# PWR_MNG_V1_0.net
KiCad netlist of a schematic drawn in Altium Designer
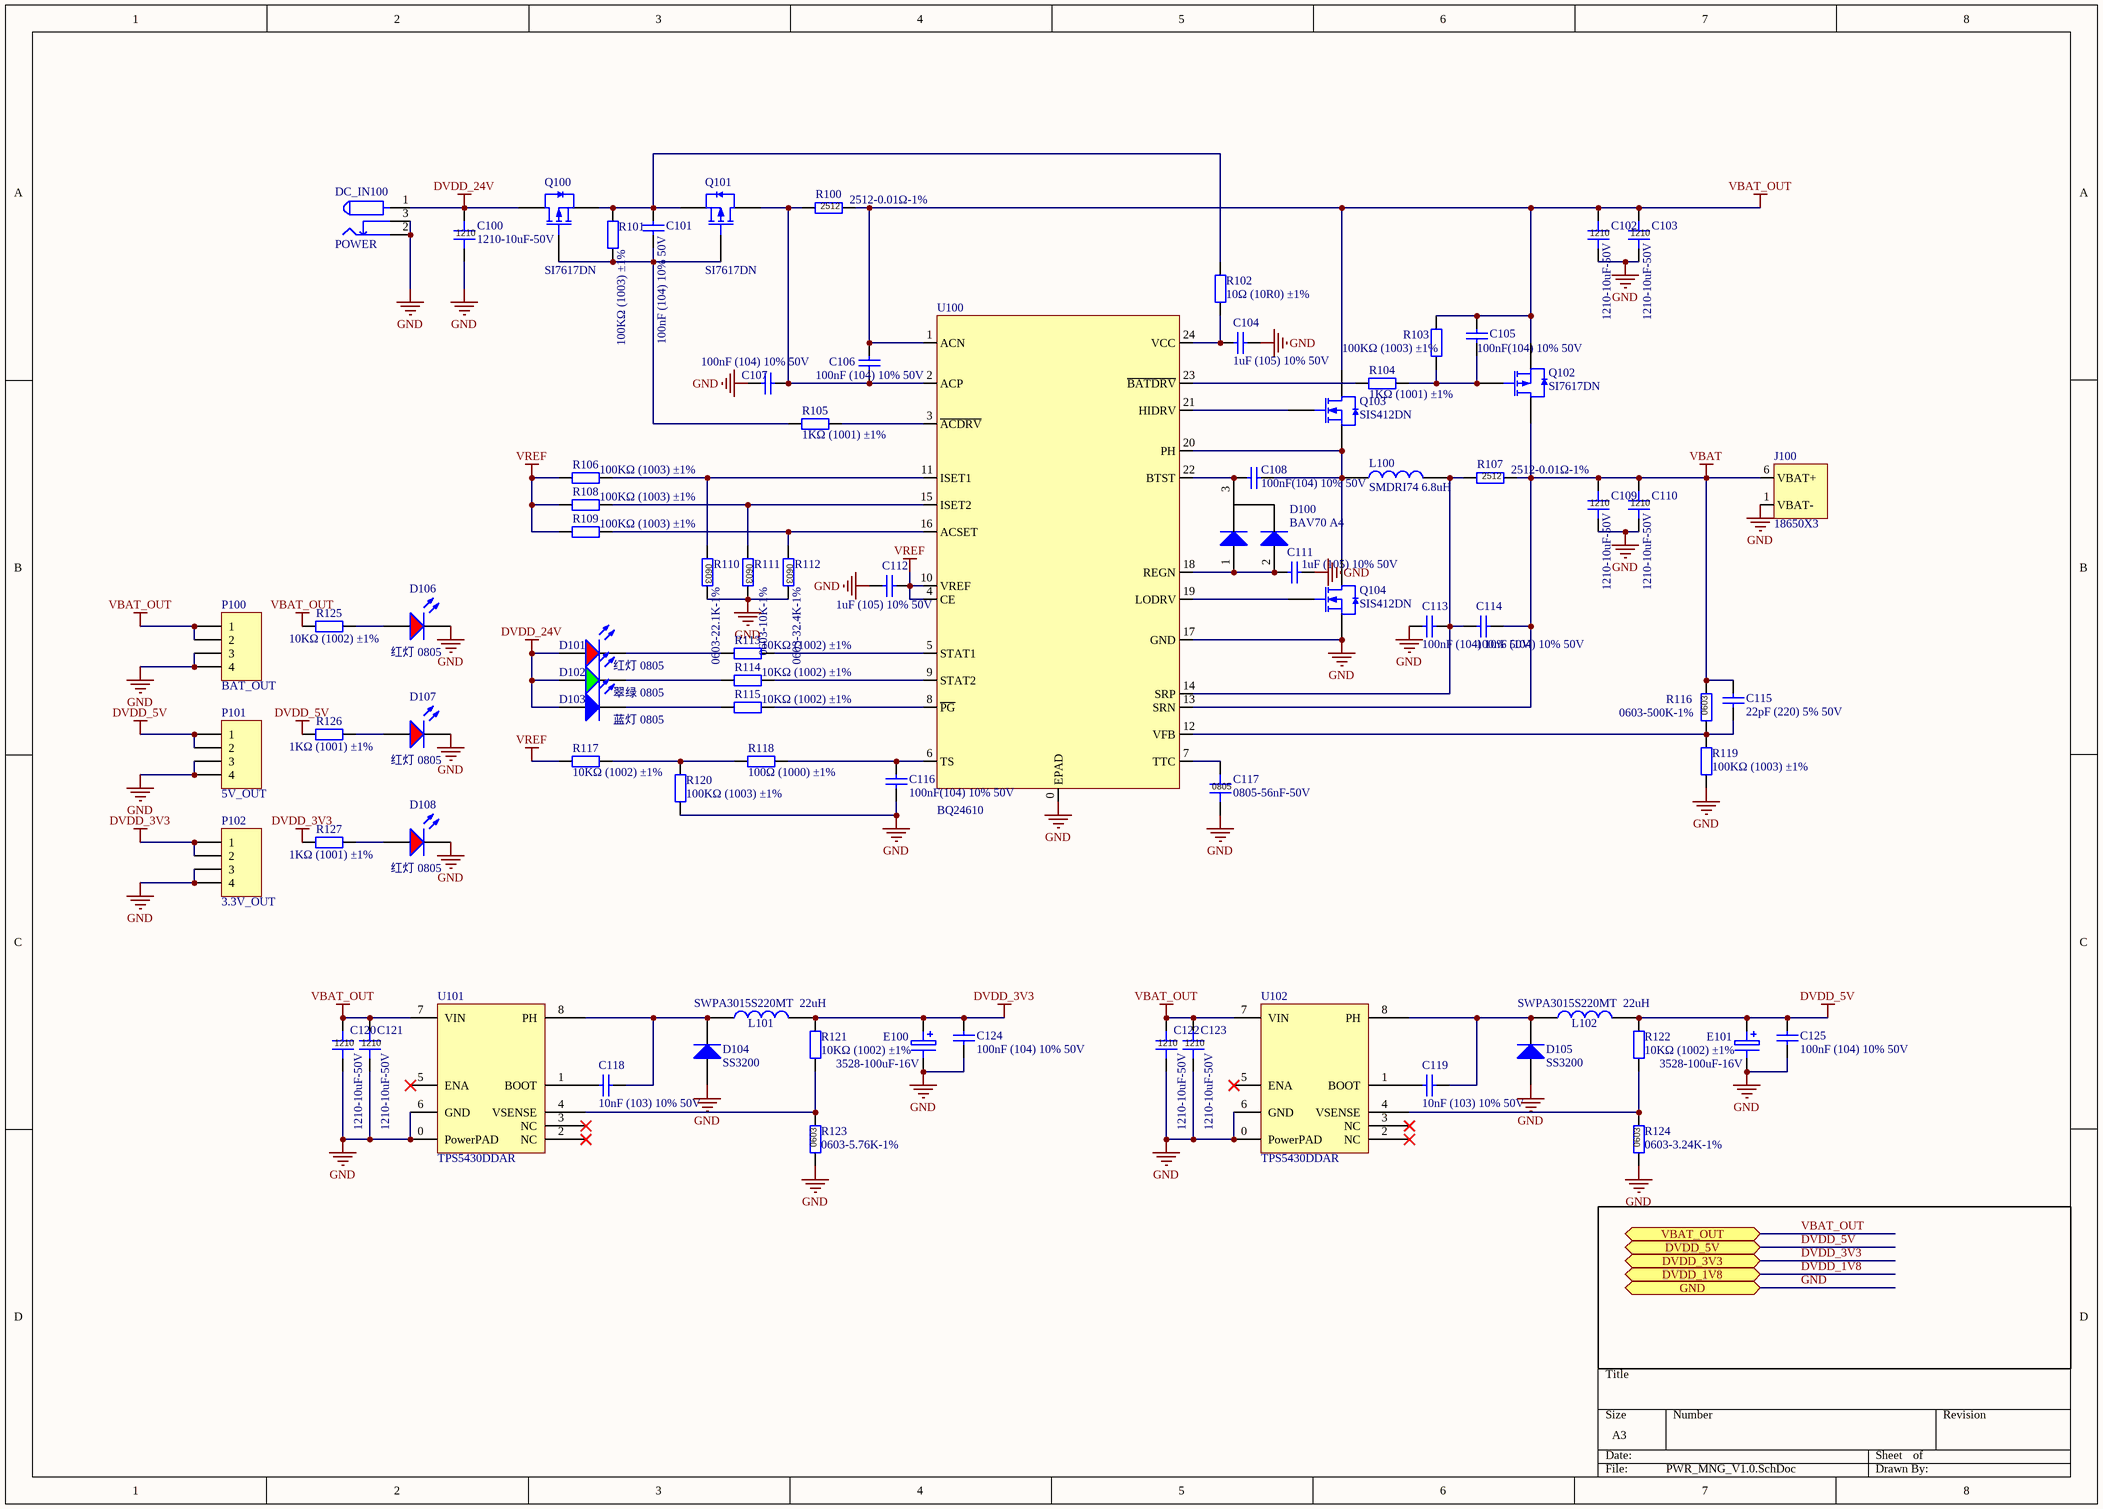
[diagram p0: PWR_MNG_V1.0.SchDoc]

(export (version "E")
  (design (tool "Eeschema 10.0.6"))
  (components
    (comp (ref "C100")
      (value "1210-10uF-50V")
      (footprint "1210_C")
      (description "贴片电容")
      (libsource (lib "JC_Integrated_Library") (part "1210 10uF (106) 10% 50V"))
    )
    (comp (ref "C101")
      (value "100nF (104) 10% 50V")
      (footprint "0603_C")
      (description "贴片电容")
      (libsource (lib "Miscellaneous Devices LC") (part "0603 100nF (104) 10% 50V"))
    )
    (comp (ref "C102")
      (value "1210-10uF-50V")
      (footprint "1210_C")
      (description "贴片电容")
      (libsource (lib "JC_Integrated_Library") (part "1210 10uF (106) 10% 50V"))
    )
    (comp (ref "C103")
      (value "1210-10uF-50V")
      (footprint "1210_C")
      (description "贴片电容")
      (libsource (lib "JC_Integrated_Library") (part "1210 10uF (106) 10% 50V"))
    )
    (comp (ref "C104")
      (value "1uF (105) 10% 50V")
      (footprint "0805_C")
      (description "贴片电容")
      (libsource (lib "Miscellaneous Devices LC") (part "0805 1uF (105) 10% 50V"))
    )
    (comp (ref "C105")
      (value "100nF(104) 10% 50V")
      (footprint "0805_C")
      (description "贴片电容")
      (libsource (lib "Miscellaneous Devices LC") (part "0805 100nF(104) 10% 50V"))
    )
    (comp (ref "C106")
      (value "100nF (104) 10% 50V")
      (footprint "0603_C")
      (description "贴片电容")
      (libsource (lib "Miscellaneous Devices LC") (part "0603 100nF (104) 10% 50V"))
    )
    (comp (ref "C107")
      (value "100nF (104) 10% 50V")
      (footprint "0603_C")
      (description "贴片电容")
      (libsource (lib "Miscellaneous Devices LC") (part "0603 100nF (104) 10% 50V"))
    )
    (comp (ref "C108")
      (value "100nF(104) 10% 50V")
      (footprint "0805_C")
      (description "贴片电容")
      (libsource (lib "Miscellaneous Devices LC") (part "0805 100nF(104) 10% 50V"))
    )
    (comp (ref "C109")
      (value "1210-10uF-50V")
      (footprint "1210_C")
      (description "贴片电容")
      (libsource (lib "JC_Integrated_Library") (part "1210 10uF (106) 10% 50V"))
    )
    (comp (ref "C110")
      (value "1210-10uF-50V")
      (footprint "1210_C")
      (description "贴片电容")
      (libsource (lib "JC_Integrated_Library") (part "1210 10uF (106) 10% 50V"))
    )
    (comp (ref "C111")
      (value "1uF (105) 10% 50V")
      (footprint "0805_C")
      (description "贴片电容")
      (libsource (lib "Miscellaneous Devices LC") (part "0805 1uF (105) 10% 50V"))
    )
    (comp (ref "C112")
      (value "1uF (105) 10% 50V")
      (footprint "0805_C")
      (description "贴片电容")
      (libsource (lib "Miscellaneous Devices LC") (part "0805 1uF (105) 10% 50V"))
    )
    (comp (ref "C113")
      (value "100nF (104) 10% 50V")
      (footprint "0603_C")
      (description "贴片电容")
      (libsource (lib "Miscellaneous Devices LC") (part "0603 100nF (104) 10% 50V"))
    )
    (comp (ref "C114")
      (value "100nF (104) 10% 50V")
      (footprint "0603_C")
      (description "贴片电容")
      (libsource (lib "Miscellaneous Devices LC") (part "0603 100nF (104) 10% 50V"))
    )
    (comp (ref "C115")
      (value "22pF (220) 5% 50V")
      (footprint "0603_C")
      (description "贴片电容")
      (libsource (lib "Miscellaneous Devices LC") (part "0603 22pF (220) 5% 50V"))
    )
    (comp (ref "C116")
      (value "100nF(104) 10% 50V")
      (footprint "0805_C")
      (description "贴片电容")
      (libsource (lib "Miscellaneous Devices LC") (part "0805 100nF(104) 10% 50V"))
    )
    (comp (ref "C117")
      (value "0805-56nF-50V")
      (footprint "0805_C")
      (description "贴片电容")
      (libsource (lib "JC_Integrated_Library") (part "0805 100nF (104) 10% 50V"))
    )
    (comp (ref "C118")
      (value "10nF (103) 10% 50V")
      (footprint "0603_C")
      (description "贴片电容")
      (libsource (lib "Miscellaneous Devices LC") (part "0603 10nF (103) 10% 50V"))
    )
    (comp (ref "C119")
      (value "10nF (103) 10% 50V")
      (footprint "0603_C")
      (description "贴片电容")
      (libsource (lib "Miscellaneous Devices LC") (part "0603 10nF (103) 10% 50V"))
    )
    (comp (ref "C120")
      (value "1210-10uF-50V")
      (footprint "1210_C")
      (description "贴片电容")
      (libsource (lib "JC_Integrated_Library") (part "1210 10uF (106) 10% 50V"))
    )
    (comp (ref "C121")
      (value "1210-10uF-50V")
      (footprint "1210_C")
      (description "贴片电容")
      (libsource (lib "JC_Integrated_Library") (part "1210 10uF (106) 10% 50V"))
    )
    (comp (ref "C122")
      (value "1210-10uF-50V")
      (footprint "1210_C")
      (description "贴片电容")
      (libsource (lib "JC_Integrated_Library") (part "1210 10uF (106) 10% 50V"))
    )
    (comp (ref "C123")
      (value "1210-10uF-50V")
      (footprint "1210_C")
      (description "贴片电容")
      (libsource (lib "JC_Integrated_Library") (part "1210 10uF (106) 10% 50V"))
    )
    (comp (ref "C124")
      (value "100nF (104) 10% 50V")
      (footprint "0603_C")
      (description "贴片电容")
      (libsource (lib "Miscellaneous Devices LC") (part "0603 100nF (104) 10% 50V"))
    )
    (comp (ref "C125")
      (value "100nF (104) 10% 50V")
      (footprint "0603_C")
      (description "贴片电容")
      (libsource (lib "Miscellaneous Devices LC") (part "0603 100nF (104) 10% 50V"))
    )
    (comp (ref "D100")
      (value "BAV70 A4")
      (footprint "SOT-23(SOT-23-3)")
      (description "开关二极管")
      (libsource (lib "Miscellaneous Devices LC") (part "SOT-23 BAV70 A4"))
    )
    (comp (ref "D101")
      (value "红灯 0805")
      (footprint "0805_LED_S1")
      (description "发光二极管")
      (libsource (lib "Miscellaneous Devices LC") (part "0805 红灯"))
    )
    (comp (ref "D102")
      (value "翠绿 0805")
      (footprint "0805_LED_S1")
      (description "发光二极管")
      (libsource (lib "Miscellaneous Devices LC") (part "0805 翠绿"))
    )
    (comp (ref "D103")
      (value "蓝灯 0805")
      (footprint "0805_LED_S1")
      (description "发光二极管")
      (libsource (lib "Miscellaneous Devices LC") (part "0805 蓝灯"))
    )
    (comp (ref "D104")
      (value "SS3200")
      (footprint "SMA(DO-214AC)_S1")
      (description "二极管")
      (libsource (lib "Miscellaneous Devices LC") (part "SMA(DO-214AC) M7"))
    )
    (comp (ref "D105")
      (value "SS3200")
      (footprint "SMA(DO-214AC)_S1")
      (description "二极管")
      (libsource (lib "Miscellaneous Devices LC") (part "SMA(DO-214AC) M7"))
    )
    (comp (ref "D106")
      (value "红灯 0805")
      (footprint "0805_LED_S1")
      (description "发光二极管")
      (libsource (lib "Miscellaneous Devices LC") (part "0805 红灯"))
    )
    (comp (ref "D107")
      (value "红灯 0805")
      (footprint "0805_LED_S1")
      (description "发光二极管")
      (libsource (lib "Miscellaneous Devices LC") (part "0805 红灯"))
    )
    (comp (ref "D108")
      (value "红灯 0805")
      (footprint "0805_LED_S1")
      (description "发光二极管")
      (libsource (lib "Miscellaneous Devices LC") (part "0805 红灯"))
    )
    (comp (ref "DC_IN100")
      (value "POWER")
      (footprint "DC002")
      (libsource (lib "JC_Integrated_Library") (part "PWR"))
    )
    (comp (ref "E100")
      (value "3528-100uF-16V")
      (footprint "ES_3528")
      (description "贴片钽电容")
      (libsource (lib "JC_Integrated_Library") (part "ES-3528"))
    )
    (comp (ref "E101")
      (value "3528-100uF-16V")
      (footprint "ES_3528")
      (description "贴片钽电容")
      (libsource (lib "JC_Integrated_Library") (part "ES-3528"))
    )
    (comp (ref "J100")
      (value "18650X3")
      (footprint "18650X3")
      (description "BAT_BASE")
      (libsource (lib "JC_Integrated_Library") (part "18650X3"))
    )
    (comp (ref "L100")
      (value "SMDRI74 6.8uH")
      (footprint "L 7.5*7.5*4.5")
      (description "贴片电感")
      (libsource (lib "JC_Integrated_Library") (part "10uH 20%"))
    )
    (comp (ref "L101")
      (value "SWPA3015S220MT  22uH")
      (footprint "L 3.0*3.0*1.5")
      (description "贴片电感")
      (libsource (lib "JC_Integrated_Library") (part "10uH 20%"))
    )
    (comp (ref "L102")
      (value "SWPA3015S220MT  22uH")
      (footprint "L 3.0*3.0*1.5")
      (description "贴片电感")
      (libsource (lib "JC_Integrated_Library") (part "10uH 20%"))
    )
    (comp (ref "P100")
      (value "BAT_OUT")
      (footprint "HDR1X4")
      (description "Header, 4-Pin")
      (fields (field (name "PUBLISHER") "Altium Limited"))
      (libsource (lib "Miscellaneous Connectors") (part "Header 4"))
    )
    (comp (ref "P101")
      (value "5V_OUT")
      (footprint "HDR1X4")
      (description "Header, 4-Pin")
      (fields (field (name "PUBLISHER") "Altium Limited"))
      (libsource (lib "Miscellaneous Connectors") (part "Header 4"))
    )
    (comp (ref "P102")
      (value "3.3V_OUT")
      (footprint "HDR1X4")
      (description "Header, 4-Pin")
      (fields (field (name "PUBLISHER") "Altium Limited"))
      (libsource (lib "Miscellaneous Connectors") (part "Header 4"))
    )
    (comp (ref "Q100")
      (value "SI7617DN")
      (footprint "PAK-1212-8")
      (description "P-MOS")
      (libsource (lib "JC_Integrated_Library") (part "SI7617DN"))
    )
    (comp (ref "Q101")
      (value "SI7617DN")
      (footprint "PAK-1212-8")
      (description "P-MOS")
      (libsource (lib "JC_Integrated_Library") (part "SI7617DN"))
    )
    (comp (ref "Q102")
      (value "SI7617DN")
      (footprint "PAK-1212-8")
      (description "P-MOS")
      (libsource (lib "JC_Integrated_Library") (part "SI7617DN"))
    )
    (comp (ref "Q103")
      (value "SIS412DN")
      (footprint "PAK-1212-8")
      (description "N-MOS")
      (libsource (lib "JC_Integrated_Library") (part "SIS412DN"))
    )
    (comp (ref "Q104")
      (value "SIS412DN")
      (footprint "PAK-1212-8")
      (description "N-MOS")
      (libsource (lib "JC_Integrated_Library") (part "SIS412DN"))
    )
    (comp (ref "R100")
      (value "2512-0.01Ω-1%")
      (footprint "2512_R")
      (description "贴片电阻")
      (libsource (lib "JC_Integrated_Library") (part "2512 10KΩ (103) 1%"))
    )
    (comp (ref "R101")
      (value "100KΩ (1003) ±1%")
      (footprint "0603_R")
      (description "贴片电阻")
      (libsource (lib "Miscellaneous Devices LC") (part "0603 100KΩ (1003) 1%"))
    )
    (comp (ref "R102")
      (value "10Ω (10R0) ±1%")
      (footprint "0805_R")
      (description "贴片电阻")
      (libsource (lib "Miscellaneous Devices LC") (part "0805 10Ω (10R0) 1%"))
    )
    (comp (ref "R103")
      (value "100KΩ (1003) ±1%")
      (footprint "0805_R")
      (description "贴片电阻")
      (libsource (lib "Miscellaneous Devices LC") (part "0805 100KΩ (1003) 1%"))
    )
    (comp (ref "R104")
      (value "1KΩ (1001) ±1%")
      (footprint "0805_R")
      (description "贴片电阻")
      (libsource (lib "Miscellaneous Devices LC") (part "0805 1KΩ (1001) 1%"))
    )
    (comp (ref "R105")
      (value "1KΩ (1001) ±1%")
      (footprint "0603_R")
      (description "贴片电阻")
      (libsource (lib "Miscellaneous Devices LC") (part "0603 1KΩ (1001) 1%"))
    )
    (comp (ref "R106")
      (value "100KΩ (1003) ±1%")
      (footprint "0603_R")
      (description "贴片电阻")
      (libsource (lib "") (part "0603 100KΩ (1003) 1%_1"))
    )
    (comp (ref "R107")
      (value "2512-0.01Ω-1%")
      (footprint "2512_R")
      (description "贴片电阻")
      (libsource (lib "JC_Integrated_Library") (part "2512 10KΩ (103) 1%"))
    )
    (comp (ref "R108")
      (value "100KΩ (1003) ±1%")
      (footprint "0603_R")
      (description "贴片电阻")
      (libsource (lib "") (part "0603 100KΩ (1003) 1%_1"))
    )
    (comp (ref "R109")
      (value "100KΩ (1003) ±1%")
      (footprint "0603_R")
      (description "贴片电阻")
      (libsource (lib "") (part "0603 100KΩ (1003) 1%_1"))
    )
    (comp (ref "R110")
      (value "0603-22.1K-1%")
      (footprint "0603_R")
      (description "贴片电阻")
      (libsource (lib "") (part "0603 10KΩ (103) 1%_1"))
    )
    (comp (ref "R111")
      (value "0603-10K-1%")
      (footprint "0603_R")
      (description "贴片电阻")
      (libsource (lib "") (part "0603 10KΩ (103) 1%_1"))
    )
    (comp (ref "R112")
      (value "0603-32.4K-1%")
      (footprint "0603_R")
      (description "贴片电阻")
      (libsource (lib "") (part "0603 10KΩ (103) 1%_1"))
    )
    (comp (ref "R113")
      (value "10KΩ (1002) ±1%")
      (footprint "0805_R")
      (description "贴片电阻")
      (libsource (lib "Miscellaneous Devices LC") (part "0805 10KΩ (1002) 1%"))
    )
    (comp (ref "R114")
      (value "10KΩ (1002) ±1%")
      (footprint "0805_R")
      (description "贴片电阻")
      (libsource (lib "Miscellaneous Devices LC") (part "0805 10KΩ (1002) 1%"))
    )
    (comp (ref "R115")
      (value "10KΩ (1002) ±1%")
      (footprint "0805_R")
      (description "贴片电阻")
      (libsource (lib "Miscellaneous Devices LC") (part "0805 10KΩ (1002) 1%"))
    )
    (comp (ref "R116")
      (value "0603-500K-1%")
      (footprint "0603_R")
      (description "贴片电阻")
      (libsource (lib "JC_Integrated_Library") (part "0603 10KΩ (103) 1%"))
    )
    (comp (ref "R117")
      (value "10KΩ (1002) ±1%")
      (footprint "0805_R")
      (description "贴片电阻")
      (libsource (lib "Miscellaneous Devices LC") (part "0805 10KΩ (1002) 1%"))
    )
    (comp (ref "R118")
      (value "100Ω (1000) ±1%")
      (footprint "0805_R")
      (description "贴片电阻")
      (libsource (lib "Miscellaneous Devices LC") (part "0805 100Ω (1000) 1%"))
    )
    (comp (ref "R119")
      (value "100KΩ (1003) ±1%")
      (footprint "0603_R")
      (description "贴片电阻")
      (libsource (lib "Miscellaneous Devices LC") (part "0603 100KΩ (1003) 1%"))
    )
    (comp (ref "R120")
      (value "100KΩ (1003) ±1%")
      (footprint "0805_R")
      (description "贴片电阻")
      (libsource (lib "Miscellaneous Devices LC") (part "0805 100KΩ (1003) 1%"))
    )
    (comp (ref "R121")
      (value "10KΩ (1002) ±1%")
      (footprint "0603_R")
      (description "贴片电阻")
      (libsource (lib "Miscellaneous Devices LC") (part "0603 10KΩ (1002) 1%"))
    )
    (comp (ref "R122")
      (value "10KΩ (1002) ±1%")
      (footprint "0603_R")
      (description "贴片电阻")
      (libsource (lib "Miscellaneous Devices LC") (part "0603 10KΩ (1002) 1%"))
    )
    (comp (ref "R123")
      (value "0603-5.76K-1%")
      (footprint "0603_R")
      (description "贴片电阻")
      (libsource (lib "JC_Integrated_Library") (part "0603 10KΩ (103) 1%"))
    )
    (comp (ref "R124")
      (value "0603-3.24K-1%")
      (footprint "0603_R")
      (description "贴片电阻")
      (libsource (lib "JC_Integrated_Library") (part "0603 10KΩ (103) 1%"))
    )
    (comp (ref "R125")
      (value "10KΩ (1002) ±1%")
      (footprint "0805_R")
      (description "贴片电阻")
      (libsource (lib "Miscellaneous Devices LC") (part "0805 10KΩ (1002) 1%"))
    )
    (comp (ref "R126")
      (value "1KΩ (1001) ±1%")
      (footprint "0805_R")
      (description "贴片电阻")
      (libsource (lib "Miscellaneous Devices LC") (part "0805 1KΩ (1001) 1%"))
    )
    (comp (ref "R127")
      (value "1KΩ (1001) ±1%")
      (footprint "0805_R")
      (description "贴片电阻")
      (libsource (lib "Miscellaneous Devices LC") (part "0805 1KΩ (1001) 1%"))
    )
    (comp (ref "U100")
      (value "BQ24610")
      (footprint "QFN-24_4x4x05P")
      (description "Charg IC")
      (libsource (lib "JC_Integrated_Library") (part "BQ24610"))
    )
    (comp (ref "U101")
      (value "TPS5430DDAR")
      (footprint "SOP-8_150mil DCDC")
      (description "DC-DC芯片")
      (libsource (lib "JC_Integrated_Library") (part "TPS5430DDAR"))
    )
    (comp (ref "U102")
      (value "TPS5430DDAR")
      (footprint "SOP-8_150mil DCDC")
      (description "DC-DC芯片")
      (libsource (lib "JC_Integrated_Library") (part "TPS5430DDAR"))
    )
  )
  (nets
    (net (code "2") (name "DVDD_3V3") (class "Default")
      (node (ref "C124") (pin "2") (pinfunction "2_2") (pintype "passive"))
      (node (ref "E100") (pin "1") (pinfunction "1_1") (pintype "passive"))
      (node (ref "L101") (pin "2") (pinfunction "2_2") (pintype "passive"))
      (node (ref "P102") (pin "1") (pinfunction "1_1") (pintype "passive"))
      (node (ref "P102") (pin "2") (pinfunction "2_2") (pintype "passive"))
      (node (ref "R121") (pin "2") (pinfunction "2_2") (pintype "passive"))
      (node (ref "R127") (pin "1") (pinfunction "1_1") (pintype "passive"))
    )
    (net (code "3") (name "DVDD_5V") (class "Default")
      (node (ref "C125") (pin "2") (pinfunction "2_2") (pintype "passive"))
      (node (ref "E101") (pin "1") (pinfunction "1_1") (pintype "passive"))
      (node (ref "L102") (pin "2") (pinfunction "2_2") (pintype "passive"))
      (node (ref "P101") (pin "1") (pinfunction "1_1") (pintype "passive"))
      (node (ref "P101") (pin "2") (pinfunction "2_2") (pintype "passive"))
      (node (ref "R122") (pin "2") (pinfunction "2_2") (pintype "passive"))
      (node (ref "R126") (pin "1") (pinfunction "1_1") (pintype "passive"))
    )
    (net (code "4") (name "DVDD_24V") (class "Default")
      (node (ref "C100") (pin "1") (pinfunction "1_1") (pintype "passive"))
      (node (ref "D101") (pin "A") (pinfunction "A_A") (pintype "passive"))
      (node (ref "D102") (pin "A") (pinfunction "A_A") (pintype "passive"))
      (node (ref "D103") (pin "A") (pinfunction "A_A") (pintype "passive"))
      (node (ref "DC_IN100") (pin "1") (pintype "passive"))
      (node (ref "Q100") (pin "3") (pinfunction "D_3") (pintype "passive"))
    )
    (net (code "5") (name "GND") (class "Default")
      (node (ref "C100") (pin "2") (pinfunction "2_2") (pintype "passive"))
      (node (ref "C102") (pin "2") (pinfunction "2_2") (pintype "passive"))
      (node (ref "C103") (pin "2") (pinfunction "2_2") (pintype "passive"))
      (node (ref "C104") (pin "2") (pinfunction "2_2") (pintype "passive"))
      (node (ref "C107") (pin "1") (pinfunction "1_1") (pintype "passive"))
      (node (ref "C109") (pin "2") (pinfunction "2_2") (pintype "passive"))
      (node (ref "C110") (pin "2") (pinfunction "2_2") (pintype "passive"))
      (node (ref "C111") (pin "1") (pinfunction "1_1") (pintype "passive"))
      (node (ref "C112") (pin "1") (pinfunction "1_1") (pintype "passive"))
      (node (ref "C113") (pin "1") (pinfunction "1_1") (pintype "passive"))
      (node (ref "C116") (pin "1") (pinfunction "1_1") (pintype "passive"))
      (node (ref "C117") (pin "2") (pinfunction "2_2") (pintype "passive"))
      (node (ref "C120") (pin "2") (pinfunction "2_2") (pintype "passive"))
      (node (ref "C121") (pin "2") (pinfunction "2_2") (pintype "passive"))
      (node (ref "C122") (pin "2") (pinfunction "2_2") (pintype "passive"))
      (node (ref "C123") (pin "2") (pinfunction "2_2") (pintype "passive"))
      (node (ref "C124") (pin "1") (pinfunction "1_1") (pintype "passive"))
      (node (ref "C125") (pin "1") (pinfunction "1_1") (pintype "passive"))
      (node (ref "D104") (pin "1") (pinfunction "A_1") (pintype "passive"))
      (node (ref "D105") (pin "1") (pinfunction "A_1") (pintype "passive"))
      (node (ref "D106") (pin "K") (pinfunction "K_K") (pintype "passive"))
      (node (ref "D107") (pin "K") (pinfunction "K_K") (pintype "passive"))
      (node (ref "D108") (pin "K") (pinfunction "K_K") (pintype "passive"))
      (node (ref "DC_IN100") (pin "2") (pintype "passive"))
      (node (ref "DC_IN100") (pin "3") (pintype "passive"))
      (node (ref "E100") (pin "2") (pinfunction "E_2") (pintype "passive"))
      (node (ref "E101") (pin "2") (pinfunction "E_2") (pintype "passive"))
      (node (ref "J100") (pin "1") (pinfunction "VBAT-_1") (pintype "passive"))
      (node (ref "P100") (pin "3") (pinfunction "3_3") (pintype "passive"))
      (node (ref "P100") (pin "4") (pinfunction "4_4") (pintype "passive"))
      (node (ref "P101") (pin "3") (pinfunction "3_3") (pintype "passive"))
      (node (ref "P101") (pin "4") (pinfunction "4_4") (pintype "passive"))
      (node (ref "P102") (pin "3") (pinfunction "3_3") (pintype "passive"))
      (node (ref "P102") (pin "4") (pinfunction "4_4") (pintype "passive"))
      (node (ref "Q104") (pin "2") (pinfunction "S_2") (pintype "passive"))
      (node (ref "R110") (pin "2") (pinfunction "2_2") (pintype "passive"))
      (node (ref "R111") (pin "2") (pinfunction "2_2") (pintype "passive"))
      (node (ref "R112") (pin "2") (pinfunction "2_2") (pintype "passive"))
      (node (ref "R119") (pin "1") (pinfunction "1_1") (pintype "passive"))
      (node (ref "R120") (pin "1") (pinfunction "1_1") (pintype "passive"))
      (node (ref "R123") (pin "1") (pinfunction "1_1") (pintype "passive"))
      (node (ref "R124") (pin "1") (pinfunction "1_1") (pintype "passive"))
      (node (ref "U100") (pin "0") (pinfunction "EPAD_0") (pintype "passive"))
      (node (ref "U100") (pin "17") (pinfunction "GND_17") (pintype "passive"))
      (node (ref "U101") (pin "0") (pinfunction "PowerPAD_0") (pintype "passive"))
      (node (ref "U101") (pin "6") (pinfunction "GND_6") (pintype "passive"))
      (node (ref "U102") (pin "0") (pinfunction "PowerPAD_0") (pintype "passive"))
      (node (ref "U102") (pin "6") (pinfunction "GND_6") (pintype "passive"))
    )
    (net (code "6") (name "Net-(D100-K)") (class "Default")
      (node (ref "C108") (pin "1") (pinfunction "1_1") (pintype "passive"))
      (node (ref "D100") (pin "3") (pinfunction "K_3") (pintype "passive"))
      (node (ref "U100") (pin "22") (pinfunction "BTST_22") (pintype "passive"))
    )
    (net (code "7") (name "Net-(D101-PadK)") (class "Default")
      (node (ref "D101") (pin "K") (pinfunction "K_K") (pintype "passive"))
      (node (ref "R113") (pin "1") (pinfunction "1_1") (pintype "passive"))
    )
    (net (code "8") (name "Net-(D102-PadK)") (class "Default")
      (node (ref "D102") (pin "K") (pinfunction "K_K") (pintype "passive"))
      (node (ref "R114") (pin "1") (pinfunction "1_1") (pintype "passive"))
    )
    (net (code "9") (name "Net-(D103-PadK)") (class "Default")
      (node (ref "D103") (pin "K") (pinfunction "K_K") (pintype "passive"))
      (node (ref "R115") (pin "1") (pinfunction "1_1") (pintype "passive"))
    )
    (net (code "10") (name "Net-(D104-K)") (class "Default")
      (node (ref "C118") (pin "2") (pinfunction "2_2") (pintype "passive"))
      (node (ref "D104") (pin "2") (pinfunction "K_2") (pintype "passive"))
      (node (ref "L101") (pin "1") (pinfunction "1_1") (pintype "passive"))
      (node (ref "U101") (pin "8") (pinfunction "PH_8") (pintype "passive"))
    )
    (net (code "11") (name "Net-(D105-K)") (class "Default")
      (node (ref "C119") (pin "2") (pinfunction "2_2") (pintype "passive"))
      (node (ref "D105") (pin "2") (pinfunction "K_2") (pintype "passive"))
      (node (ref "L102") (pin "1") (pinfunction "1_1") (pintype "passive"))
      (node (ref "U102") (pin "8") (pinfunction "PH_8") (pintype "passive"))
    )
    (net (code "12") (name "Net-(D106-PadA)") (class "Default")
      (node (ref "D106") (pin "A") (pinfunction "A_A") (pintype "passive"))
      (node (ref "R125") (pin "2") (pinfunction "2_2") (pintype "passive"))
    )
    (net (code "13") (name "Net-(D107-PadA)") (class "Default")
      (node (ref "D107") (pin "A") (pinfunction "A_A") (pintype "passive"))
      (node (ref "R126") (pin "2") (pinfunction "2_2") (pintype "passive"))
    )
    (net (code "14") (name "Net-(D108-PadA)") (class "Default")
      (node (ref "D108") (pin "A") (pinfunction "A_A") (pintype "passive"))
      (node (ref "R127") (pin "2") (pinfunction "2_2") (pintype "passive"))
    )
    (net (code "15") (name "Net-(Q100-G)") (class "Default")
      (node (ref "C101") (pin "1") (pinfunction "1_1") (pintype "passive"))
      (node (ref "Q100") (pin "1") (pinfunction "G_1") (pintype "passive"))
      (node (ref "Q101") (pin "1") (pinfunction "G_1") (pintype "passive"))
      (node (ref "R101") (pin "1") (pinfunction "1_1") (pintype "passive"))
      (node (ref "R105") (pin "2") (pinfunction "2_2") (pintype "passive"))
    )
    (net (code "16") (name "Net-(Q100-S)") (class "Default")
      (node (ref "C101") (pin "2") (pinfunction "2_2") (pintype "passive"))
      (node (ref "Q100") (pin "2") (pinfunction "S_2") (pintype "passive"))
      (node (ref "Q101") (pin "2") (pinfunction "S_2") (pintype "passive"))
      (node (ref "R101") (pin "2") (pinfunction "2_2") (pintype "passive"))
      (node (ref "R102") (pin "2") (pinfunction "2_2") (pintype "passive"))
    )
    (net (code "17") (name "Net-(Q101-D)") (class "Default")
      (node (ref "C106") (pin "1") (pinfunction "1_1") (pintype "passive"))
      (node (ref "C107") (pin "2") (pinfunction "2_2") (pintype "passive"))
      (node (ref "Q101") (pin "3") (pinfunction "D_3") (pintype "passive"))
      (node (ref "R100") (pin "1") (pinfunction "1_1") (pintype "passive"))
      (node (ref "U100") (pin "2") (pinfunction "ACP_2") (pintype "passive"))
    )
    (net (code "18") (name "Net-(Q102-G)") (class "Default")
      (node (ref "C105") (pin "1") (pinfunction "1_1") (pintype "passive"))
      (node (ref "Q102") (pin "1") (pinfunction "G_1") (pintype "passive"))
      (node (ref "R103") (pin "1") (pinfunction "1_1") (pintype "passive"))
      (node (ref "R104") (pin "2") (pinfunction "2_2") (pintype "passive"))
    )
    (net (code "19") (name "Net-(Q103-G)") (class "Default")
      (node (ref "Q103") (pin "1") (pinfunction "G_1") (pintype "passive"))
      (node (ref "U100") (pin "21") (pinfunction "HIDRV_21") (pintype "passive"))
    )
    (net (code "20") (name "Net-(Q103-S)") (class "Default")
      (node (ref "C108") (pin "2") (pinfunction "2_2") (pintype "passive"))
      (node (ref "L100") (pin "1") (pinfunction "1_1") (pintype "passive"))
      (node (ref "Q103") (pin "2") (pinfunction "S_2") (pintype "passive"))
      (node (ref "Q104") (pin "3") (pinfunction "D_3") (pintype "passive"))
      (node (ref "U100") (pin "20") (pinfunction "PH_20") (pintype "passive"))
    )
    (net (code "21") (name "Net-(Q104-G)") (class "Default")
      (node (ref "Q104") (pin "1") (pinfunction "G_1") (pintype "passive"))
      (node (ref "U100") (pin "19") (pinfunction "LODRV_19") (pintype "passive"))
    )
    (net (code "22") (name "Net-(R117-Pad2)") (class "Default")
      (node (ref "R117") (pin "2") (pinfunction "2_2") (pintype "passive"))
      (node (ref "R118") (pin "1") (pinfunction "1_1") (pintype "passive"))
      (node (ref "R120") (pin "2") (pinfunction "2_2") (pintype "passive"))
    )
    (net (code "23") (name "Net-(U100-ACSET)") (class "Default")
      (node (ref "R109") (pin "2") (pinfunction "2_2") (pintype "passive"))
      (node (ref "R112") (pin "1") (pinfunction "1_1") (pintype "passive"))
      (node (ref "U100") (pin "16") (pinfunction "ACSET_16") (pintype "passive"))
    )
    (net (code "24") (name "Net-(U100-ISET1)") (class "Default")
      (node (ref "R106") (pin "2") (pinfunction "2_2") (pintype "passive"))
      (node (ref "R110") (pin "1") (pinfunction "1_1") (pintype "passive"))
      (node (ref "U100") (pin "11") (pinfunction "ISET1_11") (pintype "passive"))
    )
    (net (code "25") (name "Net-(U100-ISET2)") (class "Default")
      (node (ref "R108") (pin "2") (pinfunction "2_2") (pintype "passive"))
      (node (ref "R111") (pin "1") (pinfunction "1_1") (pintype "passive"))
      (node (ref "U100") (pin "15") (pinfunction "ISET2_15") (pintype "passive"))
    )
    (net (code "26") (name "Net-(U100-REGN)") (class "Default")
      (node (ref "C111") (pin "2") (pinfunction "2_2") (pintype "passive"))
      (node (ref "D100") (pin "1") (pinfunction "A_1") (pintype "passive"))
      (node (ref "D100") (pin "2") (pinfunction "A_2") (pintype "passive"))
      (node (ref "U100") (pin "18") (pinfunction "REGN_18") (pintype "passive"))
    )
    (net (code "27") (name "Net-(U100-SRP)") (class "Default")
      (node (ref "C113") (pin "2") (pinfunction "2_2") (pintype "passive"))
      (node (ref "C114") (pin "1") (pinfunction "1_1") (pintype "passive"))
      (node (ref "L100") (pin "2") (pinfunction "2_2") (pintype "passive"))
      (node (ref "R107") (pin "1") (pinfunction "1_1") (pintype "passive"))
      (node (ref "U100") (pin "14") (pinfunction "SRP_14") (pintype "passive"))
    )
    (net (code "28") (name "Net-(U100-STAT1)") (class "Default")
      (node (ref "R113") (pin "2") (pinfunction "2_2") (pintype "passive"))
      (node (ref "U100") (pin "5") (pinfunction "STAT1_5") (pintype "passive"))
    )
    (net (code "29") (name "Net-(U100-STAT2)") (class "Default")
      (node (ref "R114") (pin "2") (pinfunction "2_2") (pintype "passive"))
      (node (ref "U100") (pin "9") (pinfunction "STAT2_9") (pintype "passive"))
    )
    (net (code "30") (name "Net-(U100-TS)") (class "Default")
      (node (ref "C116") (pin "2") (pinfunction "2_2") (pintype "passive"))
      (node (ref "R118") (pin "2") (pinfunction "2_2") (pintype "passive"))
      (node (ref "U100") (pin "6") (pinfunction "TS_6") (pintype "passive"))
    )
    (net (code "31") (name "Net-(U100-TTC)") (class "Default")
      (node (ref "C117") (pin "1") (pinfunction "1_1") (pintype "passive"))
      (node (ref "U100") (pin "7") (pinfunction "TTC_7") (pintype "passive"))
    )
    (net (code "32") (name "Net-(U100-VCC)") (class "Default")
      (node (ref "C104") (pin "1") (pinfunction "1_1") (pintype "passive"))
      (node (ref "R102") (pin "1") (pinfunction "1_1") (pintype "passive"))
      (node (ref "U100") (pin "24") (pinfunction "VCC_24") (pintype "passive"))
    )
    (net (code "33") (name "Net-(U100-VFB)") (class "Default")
      (node (ref "C115") (pin "1") (pinfunction "1_1") (pintype "passive"))
      (node (ref "R116") (pin "1") (pinfunction "1_1") (pintype "passive"))
      (node (ref "R119") (pin "2") (pinfunction "2_2") (pintype "passive"))
      (node (ref "U100") (pin "12") (pinfunction "VFB_12") (pintype "passive"))
    )
    (net (code "34") (name "Net-(U100-~{ACDRV})") (class "Default")
      (node (ref "R105") (pin "1") (pinfunction "1_1") (pintype "passive"))
      (node (ref "U100") (pin "3") (pinfunction "~{ACDRV}_3") (pintype "passive"))
    )
    (net (code "35") (name "Net-(U100-~{BATDRV})") (class "Default")
      (node (ref "R104") (pin "1") (pinfunction "1_1") (pintype "passive"))
      (node (ref "U100") (pin "23") (pinfunction "~{BATDRV}_23") (pintype "passive"))
    )
    (net (code "36") (name "Net-(U100-~{PG})") (class "Default")
      (node (ref "R115") (pin "2") (pinfunction "2_2") (pintype "passive"))
      (node (ref "U100") (pin "8") (pinfunction "~{PG}_8") (pintype "passive"))
    )
    (net (code "37") (name "Net-(U101-BOOT)") (class "Default")
      (node (ref "C118") (pin "1") (pinfunction "1_1") (pintype "passive"))
      (node (ref "U101") (pin "1") (pinfunction "BOOT_1") (pintype "passive"))
    )
    (net (code "38") (name "Net-(U101-VSENSE)") (class "Default")
      (node (ref "R121") (pin "1") (pinfunction "1_1") (pintype "passive"))
      (node (ref "R123") (pin "2") (pinfunction "2_2") (pintype "passive"))
      (node (ref "U101") (pin "4") (pinfunction "VSENSE_4") (pintype "passive"))
    )
    (net (code "39") (name "Net-(U102-BOOT)") (class "Default")
      (node (ref "C119") (pin "1") (pinfunction "1_1") (pintype "passive"))
      (node (ref "U102") (pin "1") (pinfunction "BOOT_1") (pintype "passive"))
    )
    (net (code "40") (name "Net-(U102-VSENSE)") (class "Default")
      (node (ref "R122") (pin "1") (pinfunction "1_1") (pintype "passive"))
      (node (ref "R124") (pin "2") (pinfunction "2_2") (pintype "passive"))
      (node (ref "U102") (pin "4") (pinfunction "VSENSE_4") (pintype "passive"))
    )
    (net (code "41") (name "VBAT") (class "Default")
      (node (ref "C109") (pin "1") (pinfunction "1_1") (pintype "passive"))
      (node (ref "C110") (pin "1") (pinfunction "1_1") (pintype "passive"))
      (node (ref "C114") (pin "2") (pinfunction "2_2") (pintype "passive"))
      (node (ref "C115") (pin "2") (pinfunction "2_2") (pintype "passive"))
      (node (ref "J100") (pin "6") (pinfunction "VBAT+_6") (pintype "passive"))
      (node (ref "Q102") (pin "3") (pinfunction "D_3") (pintype "passive"))
      (node (ref "R107") (pin "2") (pinfunction "2_2") (pintype "passive"))
      (node (ref "R116") (pin "2") (pinfunction "2_2") (pintype "passive"))
      (node (ref "U100") (pin "13") (pinfunction "SRN_13") (pintype "passive"))
    )
    (net (code "42") (name "VBAT_OUT") (class "Default")
      (node (ref "C102") (pin "1") (pinfunction "1_1") (pintype "passive"))
      (node (ref "C103") (pin "1") (pinfunction "1_1") (pintype "passive"))
      (node (ref "C105") (pin "2") (pinfunction "2_2") (pintype "passive"))
      (node (ref "C106") (pin "2") (pinfunction "2_2") (pintype "passive"))
      (node (ref "C120") (pin "1") (pinfunction "1_1") (pintype "passive"))
      (node (ref "C121") (pin "1") (pinfunction "1_1") (pintype "passive"))
      (node (ref "C122") (pin "1") (pinfunction "1_1") (pintype "passive"))
      (node (ref "C123") (pin "1") (pinfunction "1_1") (pintype "passive"))
      (node (ref "P100") (pin "1") (pinfunction "1_1") (pintype "passive"))
      (node (ref "P100") (pin "2") (pinfunction "2_2") (pintype "passive"))
      (node (ref "Q102") (pin "2") (pinfunction "S_2") (pintype "passive"))
      (node (ref "Q103") (pin "3") (pinfunction "D_3") (pintype "passive"))
      (node (ref "R100") (pin "2") (pinfunction "2_2") (pintype "passive"))
      (node (ref "R103") (pin "2") (pinfunction "2_2") (pintype "passive"))
      (node (ref "R125") (pin "1") (pinfunction "1_1") (pintype "passive"))
      (node (ref "U100") (pin "1") (pinfunction "ACN_1") (pintype "passive"))
      (node (ref "U101") (pin "7") (pinfunction "VIN_7") (pintype "passive"))
      (node (ref "U102") (pin "7") (pinfunction "VIN_7") (pintype "passive"))
    )
    (net (code "43") (name "VREF") (class "Default")
      (node (ref "C112") (pin "2") (pinfunction "2_2") (pintype "passive"))
      (node (ref "R106") (pin "1") (pinfunction "1_1") (pintype "passive"))
      (node (ref "R108") (pin "1") (pinfunction "1_1") (pintype "passive"))
      (node (ref "R109") (pin "1") (pinfunction "1_1") (pintype "passive"))
      (node (ref "R117") (pin "1") (pinfunction "1_1") (pintype "passive"))
      (node (ref "U100") (pin "10") (pinfunction "VREF_10") (pintype "passive"))
      (node (ref "U100") (pin "4") (pinfunction "CE_4") (pintype "passive"))
    )
    (net (code "44") (name "unconnected-(U101-ENA-Pad5)") (class "Default")
      (node (ref "U101") (pin "5") (pinfunction "ENA_5") (pintype "passive+no_connect"))
    )
    (net (code "45") (name "unconnected-(U101-NC-Pad2)") (class "Default")
      (node (ref "U101") (pin "2") (pinfunction "NC_2") (pintype "passive+no_connect"))
    )
    (net (code "46") (name "unconnected-(U101-NC-Pad3)") (class "Default")
      (node (ref "U101") (pin "3") (pinfunction "NC_3") (pintype "passive+no_connect"))
    )
    (net (code "47") (name "unconnected-(U102-ENA-Pad5)") (class "Default")
      (node (ref "U102") (pin "5") (pinfunction "ENA_5") (pintype "passive+no_connect"))
    )
    (net (code "48") (name "unconnected-(U102-NC-Pad2)") (class "Default")
      (node (ref "U102") (pin "2") (pinfunction "NC_2") (pintype "passive+no_connect"))
    )
    (net (code "49") (name "unconnected-(U102-NC-Pad3)") (class "Default")
      (node (ref "U102") (pin "3") (pinfunction "NC_3") (pintype "passive+no_connect"))
    )
  )
)
